# APM_BLE.net
KiCad netlist of a schematic drawn in EAGLE
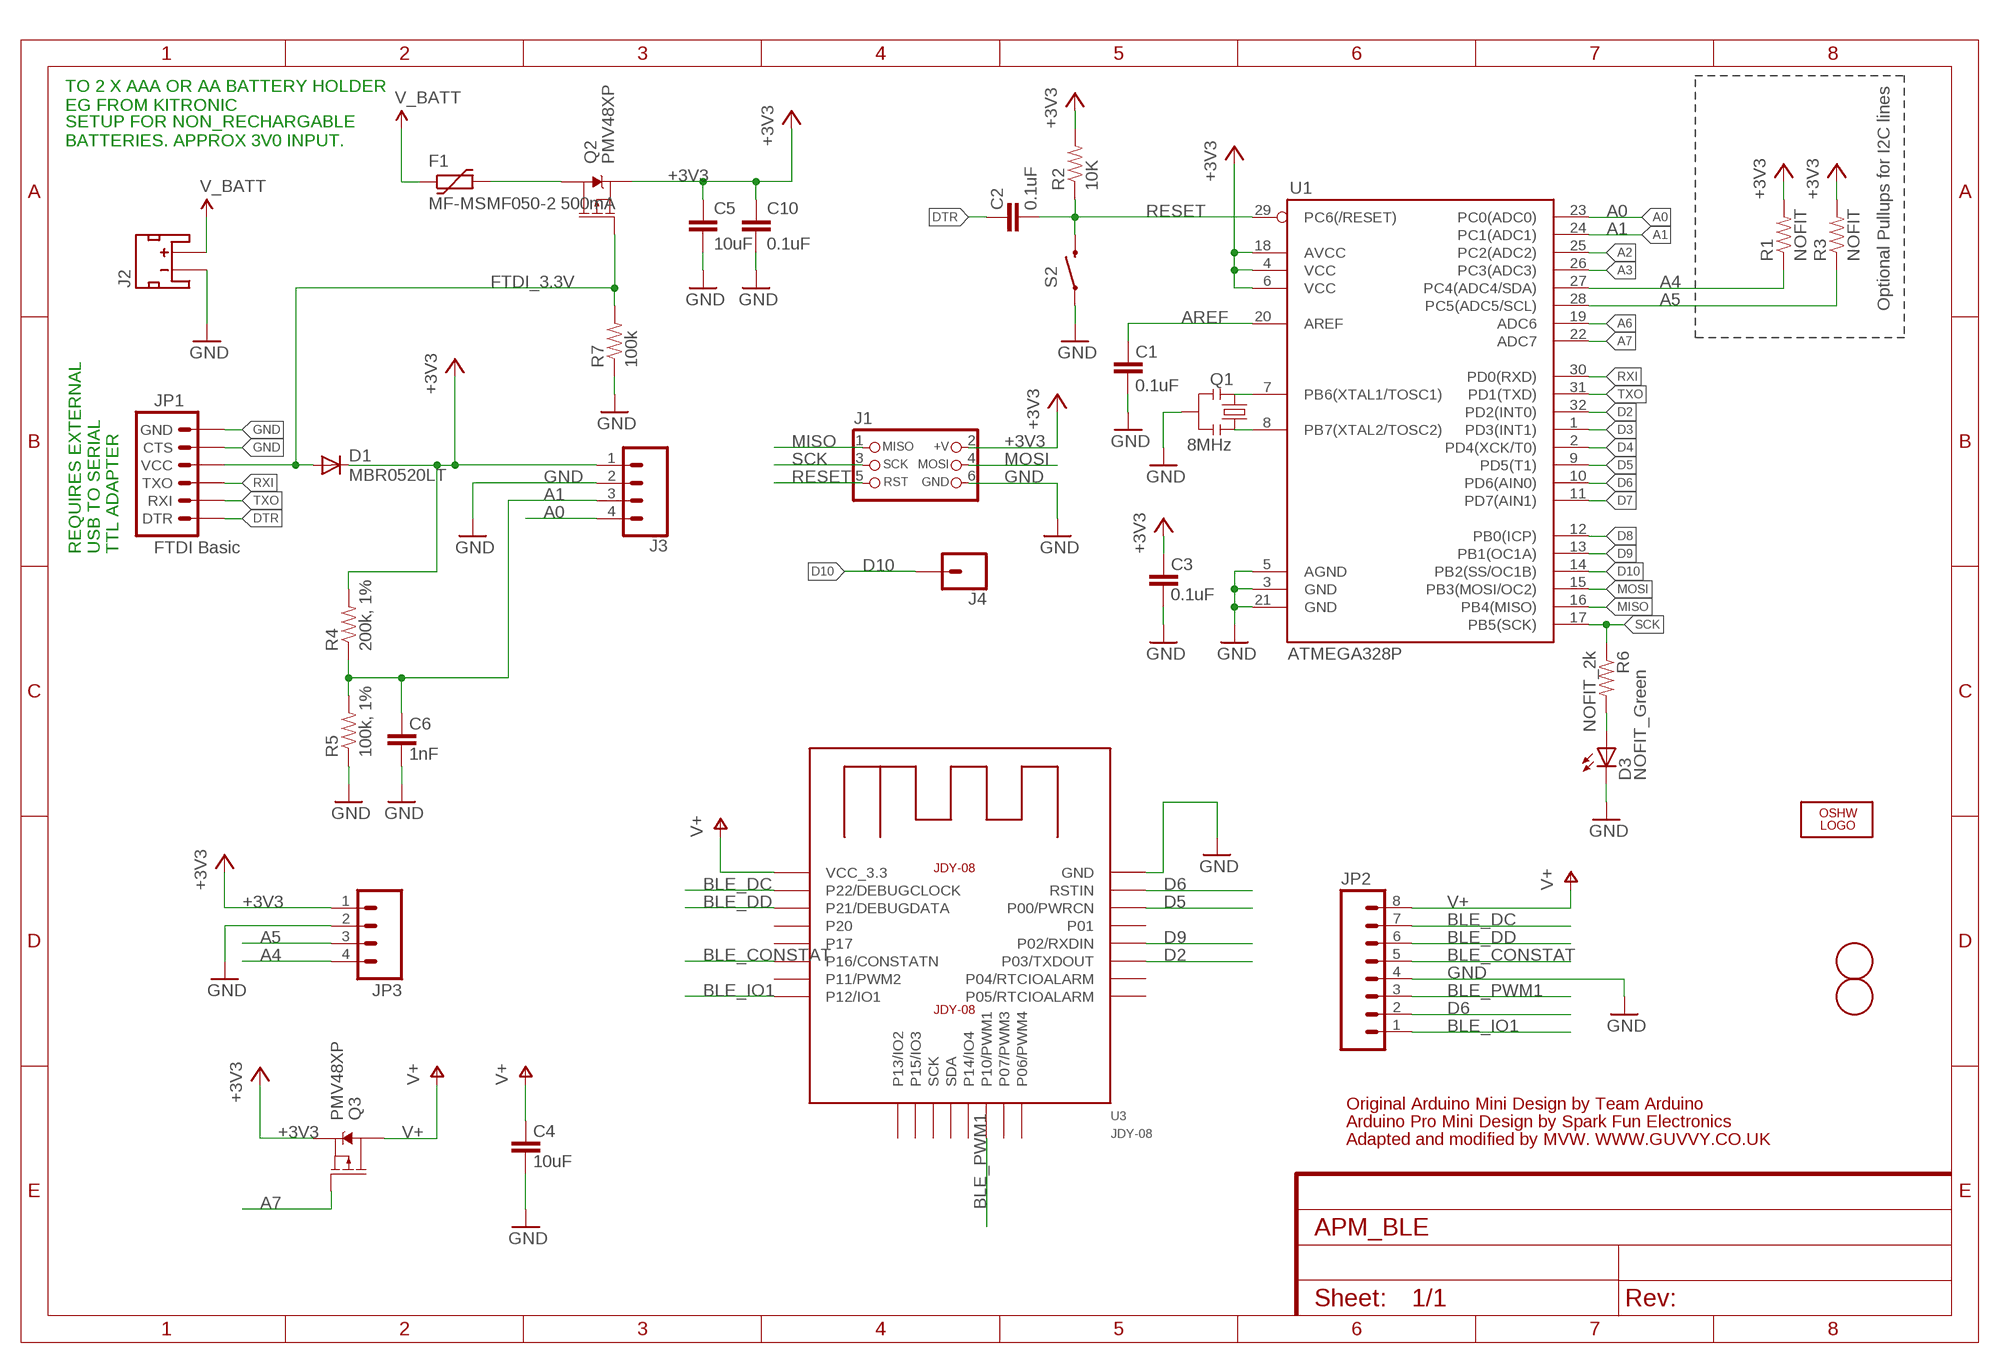
[diagram p0: schematic, sheet 1]

(export (version "E")
  (design (tool "Eeschema 10.0.6"))
  (components
    (comp (ref "C1")
      (value "0.1uF")
      (footprint "eagle-import:0603-CAP")
      (libsource (lib "eagle-import") (part "CAP0603-CAP"))
    )
    (comp (ref "C2")
      (value "0.1uF")
      (footprint "eagle-import:0603-CAP")
      (libsource (lib "eagle-import") (part "CAP0603-CAP"))
    )
    (comp (ref "C3")
      (value "0.1uF")
      (footprint "eagle-import:0603-CAP")
      (libsource (lib "eagle-import") (part "CAP0603-CAP"))
    )
    (comp (ref "C4")
      (value "10uF")
      (footprint "eagle-import:0603-CAP")
      (libsource (lib "eagle-import") (part "CAP0603-CAP"))
    )
    (comp (ref "C5")
      (value "10uF")
      (footprint "eagle-import:C0805K")
      (libsource (lib "eagle-import") (part "C-EUC0805K"))
    )
    (comp (ref "C6")
      (value "1nF")
      (footprint "eagle-import:0603-CAP")
      (libsource (lib "eagle-import") (part "CAP0603-CAP"))
    )
    (comp (ref "C10")
      (value "0.1uF")
      (footprint "eagle-import:0603-CAP")
      (libsource (lib "eagle-import") (part "CAP0603-CAP"))
    )
    (comp (ref "D1")
      (value "MBR0520LT")
      (footprint "eagle-import:SOD123")
      (libsource (lib "eagle-import") (part "MBR0520LT"))
    )
    (comp (ref "D3")
      (value "NOFIT_Green")
      (footprint "eagle-import:0603-LED-ALT1")
      (libsource (lib "eagle-import") (part "LED"))
    )
    (comp (ref "F1")
      (value "MF-MSMF050-2 500mA")
      (footprint "eagle-import:PTC1812L")
      (libsource (lib "eagle-import") (part "FUSE_PTC-1812"))
    )
    (comp (ref "FID1")
      (value "FIDUCIAL")
      (footprint "eagle-import:FIDUCIAL_1MM")
      (libsource (lib "eagle-import") (part "FIDUCIAL"))
    )
    (comp (ref "FID2")
      (value "FIDUCIAL")
      (footprint "eagle-import:FIDUCIAL_1MM")
      (libsource (lib "eagle-import") (part "FIDUCIAL"))
    )
    (comp (ref "J1")
      (value "CON_HEADER_PRG_AVR_ICSP-PTH")
      (footprint "eagle-import:HEADER_PRG_2X03")
      (libsource (lib "eagle-import") (part "CON_HEADER_PRG_AVR_ICSP-PTH"))
    )
    (comp (ref "J2")
      (value "B2B-PH-K-S(LF)(SN)")
      (footprint "eagle-import:JST-2-SMD")
      (libsource (lib "eagle-import") (part "JST_2MM_MALE"))
    )
    (comp (ref "J3")
      (value "CONN_04")
      (footprint "eagle-import:1X04")
      (libsource (lib "eagle-import") (part "CONN_04"))
    )
    (comp (ref "J4")
      (value "CONN_01")
      (footprint "eagle-import:1X01")
      (libsource (lib "eagle-import") (part "CONN_01"))
    )
    (comp (ref "JP1")
      (value "FTDI Basic")
      (footprint "eagle-import:1X06")
      (libsource (lib "eagle-import") (part "ARDUINO_SERIAL_PROGRAMPTH"))
    )
    (comp (ref "JP2")
      (value "M08BM08B-SRSS-TB")
      (footprint "eagle-import:BM08B-SRSS-TB")
      (libsource (lib "eagle-import") (part "M08BM08B-SRSS-TB"))
    )
    (comp (ref "JP3")
      (value "M04PTH")
      (footprint "eagle-import:1X04")
      (libsource (lib "eagle-import") (part "M04PTH"))
    )
    (comp (ref "LOGO1")
      (value "OSHW_LOGO_FILLX0200-NT")
      (footprint "eagle-import:OSHW_FILLX200_NOTEXT")
      (libsource (lib "eagle-import") (part "OSHW_LOGO_FILLX0200-NT"))
    )
    (comp (ref "Q1")
      (value "8MHz")
      (footprint "eagle-import:RESONATOR-SMD-1_1")
      (libsource (lib "eagle-import") (part "RESONATOR1{colon}1"))
    )
    (comp (ref "Q2")
      (value "PMV48XP")
      (footprint "eagle-import:SOT23-3")
      (libsource (lib "eagle-import") (part "MOSFET_PCH-IRLML2244"))
    )
    (comp (ref "Q3")
      (value "PMV48XP")
      (footprint "eagle-import:SOT23-3")
      (libsource (lib "eagle-import") (part "MOSFET_PCH-IRLML2244"))
    )
    (comp (ref "R1")
      (value "NOFIT")
      (footprint "eagle-import:0603-RES")
      (libsource (lib "eagle-import") (part "RESISTOR0603-RES"))
    )
    (comp (ref "R2")
      (value "10K")
      (footprint "eagle-import:0603-RES")
      (libsource (lib "eagle-import") (part "RESISTOR0603-RES"))
    )
    (comp (ref "R3")
      (value "NOFIT")
      (footprint "eagle-import:0603-RES")
      (libsource (lib "eagle-import") (part "RESISTOR0603-RES"))
    )
    (comp (ref "R4")
      (value "200k, 1%")
      (footprint "eagle-import:0603-RES")
      (libsource (lib "eagle-import") (part "RESISTOR0603-RES"))
    )
    (comp (ref "R5")
      (value "100k, 1%")
      (footprint "eagle-import:0603-RES")
      (libsource (lib "eagle-import") (part "RESISTOR0603-RES"))
    )
    (comp (ref "R6")
      (value "NOFIT_2k")
      (footprint "eagle-import:0603-RES")
      (libsource (lib "eagle-import") (part "RESISTOR0603-RES"))
    )
    (comp (ref "R7")
      (value "100k")
      (footprint "eagle-import:0603-RES")
      (libsource (lib "eagle-import") (part "RESISTOR0603-RES"))
    )
    (comp (ref "S2")
      (value "SWITCH-MOMENTARY-2TACTILE-SWITCH-SMD-RIGHT-ANGLE")
      (footprint "eagle-import:TACTILE_SWITCH-SMD-RIGHT-ANGLE")
      (libsource (lib "eagle-import") (part "SWITCH-MOMENTARY-2TACTILE-SWITCH-SMD-RIGHT-ANGLE"))
    )
    (comp (ref "U1")
      (value "ATMEGA328P")
      (footprint "eagle-import:TQFP32-08")
      (libsource (lib "eagle-import") (part "ATMEGA168"))
    )
    (comp (ref "U3")
      (value "JDY-08")
      (footprint "eagle-import:JDY-08")
      (libsource (lib "eagle-import") (part "JDY-08"))
    )
  )
  (nets
    (net (code "1") (name "+3V3") (class "Default")
      (node (ref "C10") (pin "1") (pinfunction "1_1") (pintype "passive"))
      (node (ref "C3") (pin "2") (pinfunction "2_2") (pintype "passive"))
      (node (ref "C5") (pin "1") (pinfunction "1_1") (pintype "passive"))
      (node (ref "D1") (pin "C") (pinfunction "C_C") (pintype "passive"))
      (node (ref "J1") (pin "2") (pinfunction "+V_2") (pintype "passive"))
      (node (ref "J3") (pin "1") (pinfunction "1_1") (pintype "passive"))
      (node (ref "JP3") (pin "1") (pinfunction "1_1") (pintype "passive"))
      (node (ref "Q2") (pin "2") (pinfunction "S_2") (pintype "bidirectional"))
      (node (ref "Q3") (pin "2") (pinfunction "S_2") (pintype "bidirectional"))
      (node (ref "R1") (pin "2") (pinfunction "2_2") (pintype "passive"))
      (node (ref "R2") (pin "2") (pinfunction "2_2") (pintype "passive"))
      (node (ref "R3") (pin "2") (pinfunction "2_2") (pintype "passive"))
      (node (ref "R4") (pin "2") (pinfunction "2_2") (pintype "passive"))
      (node (ref "U1") (pin "18") (pinfunction "AVCC_18") (pintype "bidirectional"))
      (node (ref "U1") (pin "4") (pinfunction "VCC_4") (pintype "bidirectional"))
      (node (ref "U1") (pin "6") (pinfunction "VCC_6") (pintype "bidirectional"))
    )
    (net (code "2") (name "/A4") (class "Default")
      (node (ref "JP3") (pin "4") (pinfunction "4_4") (pintype "passive"))
      (node (ref "R1") (pin "1") (pinfunction "1_1") (pintype "passive"))
      (node (ref "U1") (pin "27") (pinfunction "PC4(ADC4/SDA)_27") (pintype "bidirectional"))
    )
    (net (code "3") (name "/A5") (class "Default")
      (node (ref "JP3") (pin "3") (pinfunction "3_3") (pintype "passive"))
      (node (ref "R3") (pin "1") (pinfunction "1_1") (pintype "passive"))
      (node (ref "U1") (pin "28") (pinfunction "PC5(ADC5/SCL)_28") (pintype "bidirectional"))
    )
    (net (code "4") (name "/AREF") (class "Default")
      (node (ref "C1") (pin "2") (pinfunction "2_2") (pintype "passive"))
      (node (ref "U1") (pin "20") (pinfunction "AREF_20") (pintype "bidirectional"))
    )
    (net (code "5") (name "/BLE_CONSTAT") (class "Default")
      (node (ref "JP2") (pin "5") (pinfunction "5_5") (pintype "passive"))
      (node (ref "U3") (pin "P16/CONSTATN") (pinfunction "P16/CONSTATN_P16/CONSTATN") (pintype "bidirectional"))
    )
    (net (code "6") (name "/BLE_DC") (class "Default")
      (node (ref "JP2") (pin "7") (pinfunction "7_7") (pintype "passive"))
      (node (ref "U3") (pin "P22/DEBUGCLOCK") (pinfunction "P22/DEBUGCLOCK_P22/DEBUGCLOCK") (pintype "bidirectional"))
    )
    (net (code "7") (name "/BLE_DD") (class "Default")
      (node (ref "JP2") (pin "6") (pinfunction "6_6") (pintype "passive"))
      (node (ref "U3") (pin "P21/DEBUGDATA") (pinfunction "P21/DEBUGDATA_P21/DEBUGDATA") (pintype "bidirectional"))
    )
    (net (code "8") (name "/BLE_IO1") (class "Default")
      (node (ref "JP2") (pin "1") (pinfunction "1_1") (pintype "passive"))
      (node (ref "U3") (pin "P12/IO1") (pinfunction "P12/IO1_P12/IO1") (pintype "bidirectional"))
    )
    (net (code "9") (name "/BLE_PWM1") (class "Default")
      (node (ref "JP2") (pin "3") (pinfunction "3_3") (pintype "passive"))
      (node (ref "U3") (pin "P10/PWM1") (pinfunction "P10/PWM1_P10/PWM1") (pintype "bidirectional"))
    )
    (net (code "10") (name "/FTDI_3.3V") (class "Default")
      (node (ref "D1") (pin "A") (pinfunction "A_A") (pintype "passive"))
      (node (ref "JP1") (pin "4") (pinfunction "VCC_4") (pintype "passive"))
      (node (ref "Q2") (pin "1") (pinfunction "G_1") (pintype "bidirectional"))
      (node (ref "R7") (pin "2") (pinfunction "2_2") (pintype "passive"))
    )
    (net (code "11") (name "/RESET") (class "Default")
      (node (ref "C2") (pin "1") (pinfunction "1_1") (pintype "passive"))
      (node (ref "J1") (pin "5") (pinfunction "RST_5") (pintype "passive"))
      (node (ref "R2") (pin "1") (pinfunction "1_1") (pintype "passive"))
      (node (ref "S2") (pin "2") (pinfunction "2_2") (pintype "passive"))
      (node (ref "U1") (pin "29") (pinfunction "PC6(/RESET)_29") (pintype "bidirectional"))
    )
    (net (code "12") (name "A0") (class "Default")
      (node (ref "J3") (pin "4") (pinfunction "4_4") (pintype "passive"))
      (node (ref "U1") (pin "23") (pinfunction "PC0(ADC0)_23") (pintype "bidirectional"))
    )
    (net (code "13") (name "A1") (class "Default")
      (node (ref "C6") (pin "2") (pinfunction "2_2") (pintype "passive"))
      (node (ref "J3") (pin "3") (pinfunction "3_3") (pintype "passive"))
      (node (ref "R4") (pin "1") (pinfunction "1_1") (pintype "passive"))
      (node (ref "R5") (pin "2") (pinfunction "2_2") (pintype "passive"))
      (node (ref "U1") (pin "24") (pinfunction "PC1(ADC1)_24") (pintype "bidirectional"))
    )
    (net (code "14") (name "A2") (class "Default")
      (node (ref "U1") (pin "25") (pinfunction "PC2(ADC2)_25") (pintype "bidirectional"))
    )
    (net (code "15") (name "A3") (class "Default")
      (node (ref "U1") (pin "26") (pinfunction "PC3(ADC3)_26") (pintype "bidirectional"))
    )
    (net (code "16") (name "A6") (class "Default")
      (node (ref "U1") (pin "19") (pinfunction "ADC6_19") (pintype "bidirectional"))
    )
    (net (code "17") (name "A7") (class "Default")
      (node (ref "Q3") (pin "1") (pinfunction "G_1") (pintype "bidirectional"))
      (node (ref "U1") (pin "22") (pinfunction "ADC7_22") (pintype "bidirectional"))
    )
    (net (code "18") (name "D2") (class "Default")
      (node (ref "U1") (pin "32") (pinfunction "PD2(INT0)_32") (pintype "bidirectional"))
      (node (ref "U3") (pin "P03/TXDOUT") (pinfunction "P03/TXDOUT_P03/TXDOUT") (pintype "bidirectional"))
    )
    (net (code "19") (name "D3") (class "Default")
      (node (ref "U1") (pin "1") (pinfunction "PD3(INT1)_1") (pintype "bidirectional"))
    )
    (net (code "20") (name "D4") (class "Default")
      (node (ref "U1") (pin "2") (pinfunction "PD4(XCK/T0)_2") (pintype "bidirectional"))
    )
    (net (code "21") (name "D5") (class "Default")
      (node (ref "U1") (pin "9") (pinfunction "PD5(T1)_9") (pintype "bidirectional"))
      (node (ref "U3") (pin "P00/PWRCN") (pinfunction "P00/PWRCN_P00/PWRCN") (pintype "bidirectional"))
    )
    (net (code "22") (name "D6") (class "Default")
      (node (ref "JP2") (pin "2") (pinfunction "2_2") (pintype "passive"))
      (node (ref "U1") (pin "10") (pinfunction "PD6(AIN0)_10") (pintype "bidirectional"))
      (node (ref "U3") (pin "RSTIN") (pinfunction "RSTIN_RSTIN") (pintype "bidirectional"))
    )
    (net (code "23") (name "D7") (class "Default")
      (node (ref "U1") (pin "11") (pinfunction "PD7(AIN1)_11") (pintype "bidirectional"))
    )
    (net (code "24") (name "D8") (class "Default")
      (node (ref "U1") (pin "12") (pinfunction "PB0(ICP)_12") (pintype "bidirectional"))
    )
    (net (code "25") (name "D9") (class "Default")
      (node (ref "U1") (pin "13") (pinfunction "PB1(OC1A)_13") (pintype "bidirectional"))
      (node (ref "U3") (pin "P02/RXDIN") (pinfunction "P02/RXDIN_P02/RXDIN") (pintype "bidirectional"))
    )
    (net (code "26") (name "D10") (class "Default")
      (node (ref "J4") (pin "1") (pinfunction "1_1") (pintype "passive"))
      (node (ref "U1") (pin "14") (pinfunction "PB2(SS/OC1B)_14") (pintype "bidirectional"))
    )
    (net (code "27") (name "DTR") (class "Default")
      (node (ref "C2") (pin "2") (pinfunction "2_2") (pintype "passive"))
      (node (ref "JP1") (pin "1") (pinfunction "DTR_1") (pintype "passive"))
    )
    (net (code "28") (name "GND") (class "Default")
      (node (ref "C1") (pin "1") (pinfunction "1_1") (pintype "passive"))
      (node (ref "C10") (pin "2") (pinfunction "2_2") (pintype "passive"))
      (node (ref "C3") (pin "1") (pinfunction "1_1") (pintype "passive"))
      (node (ref "C4") (pin "1") (pinfunction "1_1") (pintype "passive"))
      (node (ref "C5") (pin "2") (pinfunction "2_2") (pintype "passive"))
      (node (ref "C6") (pin "1") (pinfunction "1_1") (pintype "passive"))
      (node (ref "D3") (pin "C") (pinfunction "C_C") (pintype "passive"))
      (node (ref "J1") (pin "6") (pinfunction "GND_6") (pintype "passive"))
      (node (ref "J2") (pin "1") (pinfunction "-_1") (pintype "bidirectional"))
      (node (ref "J3") (pin "2") (pinfunction "2_2") (pintype "passive"))
      (node (ref "JP1") (pin "5") (pinfunction "CTS_5") (pintype "passive"))
      (node (ref "JP1") (pin "6") (pinfunction "GND_6") (pintype "passive"))
      (node (ref "JP2") (pin "4") (pinfunction "4_4") (pintype "passive"))
      (node (ref "JP3") (pin "2") (pinfunction "2_2") (pintype "passive"))
      (node (ref "Q1") (pin "2") (pinfunction "2_2") (pintype "passive"))
      (node (ref "R5") (pin "1") (pinfunction "1_1") (pintype "passive"))
      (node (ref "R7") (pin "1") (pinfunction "1_1") (pintype "passive"))
      (node (ref "S2") (pin "1") (pinfunction "1_1") (pintype "passive"))
      (node (ref "U1") (pin "21") (pinfunction "GND_21") (pintype "bidirectional"))
      (node (ref "U1") (pin "3") (pinfunction "GND_3") (pintype "bidirectional"))
      (node (ref "U1") (pin "5") (pinfunction "AGND_5") (pintype "bidirectional"))
      (node (ref "U3") (pin "GND") (pinfunction "GND_GND") (pintype "bidirectional"))
    )
    (net (code "29") (name "MISO") (class "Default")
      (node (ref "J1") (pin "1") (pinfunction "MISO_1") (pintype "passive"))
      (node (ref "U1") (pin "16") (pinfunction "PB4(MISO)_16") (pintype "bidirectional"))
    )
    (net (code "30") (name "MOSI") (class "Default")
      (node (ref "J1") (pin "4") (pinfunction "MOSI_4") (pintype "passive"))
      (node (ref "U1") (pin "15") (pinfunction "PB3(MOSI/OC2)_15") (pintype "bidirectional"))
    )
    (net (code "31") (name "Net-(D3-PadA)") (class "Default")
      (node (ref "D3") (pin "A") (pinfunction "A_A") (pintype "passive"))
      (node (ref "R6") (pin "2") (pinfunction "2_2") (pintype "passive"))
    )
    (net (code "32") (name "Net-(Q2-D)") (class "Default")
      (node (ref "F1") (pin "2") (pinfunction "2_2") (pintype "passive"))
      (node (ref "Q2") (pin "3") (pinfunction "D_3") (pintype "bidirectional"))
    )
    (net (code "33") (name "Net-(U1-PB6(XTAL1{slash}TOSC1))") (class "Default")
      (node (ref "Q1") (pin "1") (pinfunction "1_1") (pintype "passive"))
      (node (ref "U1") (pin "7") (pinfunction "PB6(XTAL1/TOSC1)_7") (pintype "bidirectional"))
    )
    (net (code "34") (name "Net-(U1-PB7(XTAL2{slash}TOSC2))") (class "Default")
      (node (ref "Q1") (pin "3") (pinfunction "3_3") (pintype "passive"))
      (node (ref "U1") (pin "8") (pinfunction "PB7(XTAL2/TOSC2)_8") (pintype "bidirectional"))
    )
    (net (code "35") (name "RXI") (class "Default")
      (node (ref "JP1") (pin "3") (pinfunction "TXO_3") (pintype "passive"))
      (node (ref "U1") (pin "30") (pinfunction "PD0(RXD)_30") (pintype "bidirectional"))
    )
    (net (code "36") (name "SCK") (class "Default")
      (node (ref "J1") (pin "3") (pinfunction "SCK_3") (pintype "passive"))
      (node (ref "R6") (pin "1") (pinfunction "1_1") (pintype "passive"))
      (node (ref "U1") (pin "17") (pinfunction "PB5(SCK)_17") (pintype "bidirectional"))
    )
    (net (code "37") (name "TXO") (class "Default")
      (node (ref "JP1") (pin "2") (pinfunction "RXI_2") (pintype "passive"))
      (node (ref "U1") (pin "31") (pinfunction "PD1(TXD)_31") (pintype "bidirectional"))
    )
    (net (code "38") (name "V+") (class "Default")
      (node (ref "C4") (pin "2") (pinfunction "2_2") (pintype "passive"))
      (node (ref "JP2") (pin "8") (pinfunction "8_8") (pintype "passive"))
      (node (ref "Q3") (pin "3") (pinfunction "D_3") (pintype "bidirectional"))
      (node (ref "U3") (pin "VCC_3.3") (pinfunction "VCC_3.3_VCC_3.3") (pintype "bidirectional"))
    )
    (net (code "39") (name "V_BATT") (class "Default")
      (node (ref "F1") (pin "1") (pinfunction "1_1") (pintype "passive"))
      (node (ref "J2") (pin "2") (pinfunction "+_2") (pintype "bidirectional"))
    )
    (net (code "40") (name "unconnected-(J2-PAD1-PadNC1)") (class "Default")
      (node (ref "J2") (pin "NC1") (pinfunction "PAD1_NC1") (pintype "bidirectional"))
    )
    (net (code "41") (name "unconnected-(J2-PAD2-PadNC2)") (class "Default")
      (node (ref "J2") (pin "NC2") (pinfunction "PAD2_NC2") (pintype "bidirectional"))
    )
    (net (code "42") (name "unconnected-(U3-P04{slash}RTCIOALARM-PadP04{slash}RTCALARMIO)") (class "Default")
      (node (ref "U3") (pin "P04/RTCALARMIO") (pinfunction "P04/RTCIOALARM_P04/RTCALARMIO") (pintype "bidirectional"))
    )
    (net (code "43") (name "unconnected-(U3-P05{slash}RTCIOALARM-PadP05{slash}RTCALARMIO)") (class "Default")
      (node (ref "U3") (pin "P05/RTCALARMIO") (pinfunction "P05/RTCIOALARM_P05/RTCALARMIO") (pintype "bidirectional"))
    )
    (net (code "44") (name "unconnected-(U3-PadP01)") (class "Default")
      (node (ref "U3") (pin "P01") (pinfunction "P01_P01") (pintype "bidirectional"))
    )
    (net (code "45") (name "unconnected-(U3-PadP06{slash}PWM4)") (class "Default")
      (node (ref "U3") (pin "P06/PWM4") (pinfunction "P06/PWM4_P06/PWM4") (pintype "bidirectional"))
    )
    (net (code "46") (name "unconnected-(U3-PadP07{slash}PWM3)") (class "Default")
      (node (ref "U3") (pin "P07/PWM3") (pinfunction "P07/PWM3_P07/PWM3") (pintype "bidirectional"))
    )
    (net (code "47") (name "unconnected-(U3-PadP11{slash}PWM2)") (class "Default")
      (node (ref "U3") (pin "P11/PWM2") (pinfunction "P11/PWM2_P11/PWM2") (pintype "bidirectional"))
    )
    (net (code "48") (name "unconnected-(U3-PadP13{slash}IO2)") (class "Default")
      (node (ref "U3") (pin "P13/IO2") (pinfunction "P13/IO2_P13/IO2") (pintype "bidirectional"))
    )
    (net (code "49") (name "unconnected-(U3-PadP14{slash}IO4)") (class "Default")
      (node (ref "U3") (pin "P14/IO4") (pinfunction "P14/IO4_P14/IO4") (pintype "bidirectional"))
    )
    (net (code "50") (name "unconnected-(U3-PadP15{slash}IO3)") (class "Default")
      (node (ref "U3") (pin "P15/IO3") (pinfunction "P15/IO3_P15/IO3") (pintype "bidirectional"))
    )
    (net (code "51") (name "unconnected-(U3-PadP17)") (class "Default")
      (node (ref "U3") (pin "P17") (pinfunction "P17_P17") (pintype "bidirectional"))
    )
    (net (code "52") (name "unconnected-(U3-PadP20)") (class "Default")
      (node (ref "U3") (pin "P20") (pinfunction "P20_P20") (pintype "bidirectional"))
    )
    (net (code "53") (name "unconnected-(U3-PadSCK)") (class "Default")
      (node (ref "U3") (pin "SCK") (pinfunction "SCK_SCK") (pintype "bidirectional"))
    )
    (net (code "54") (name "unconnected-(U3-PadSDA)") (class "Default")
      (node (ref "U3") (pin "SDA") (pinfunction "SDA_SDA") (pintype "bidirectional"))
    )
  )
)
